# Power.net
KiCad netlist of a schematic drawn in Altium Designer
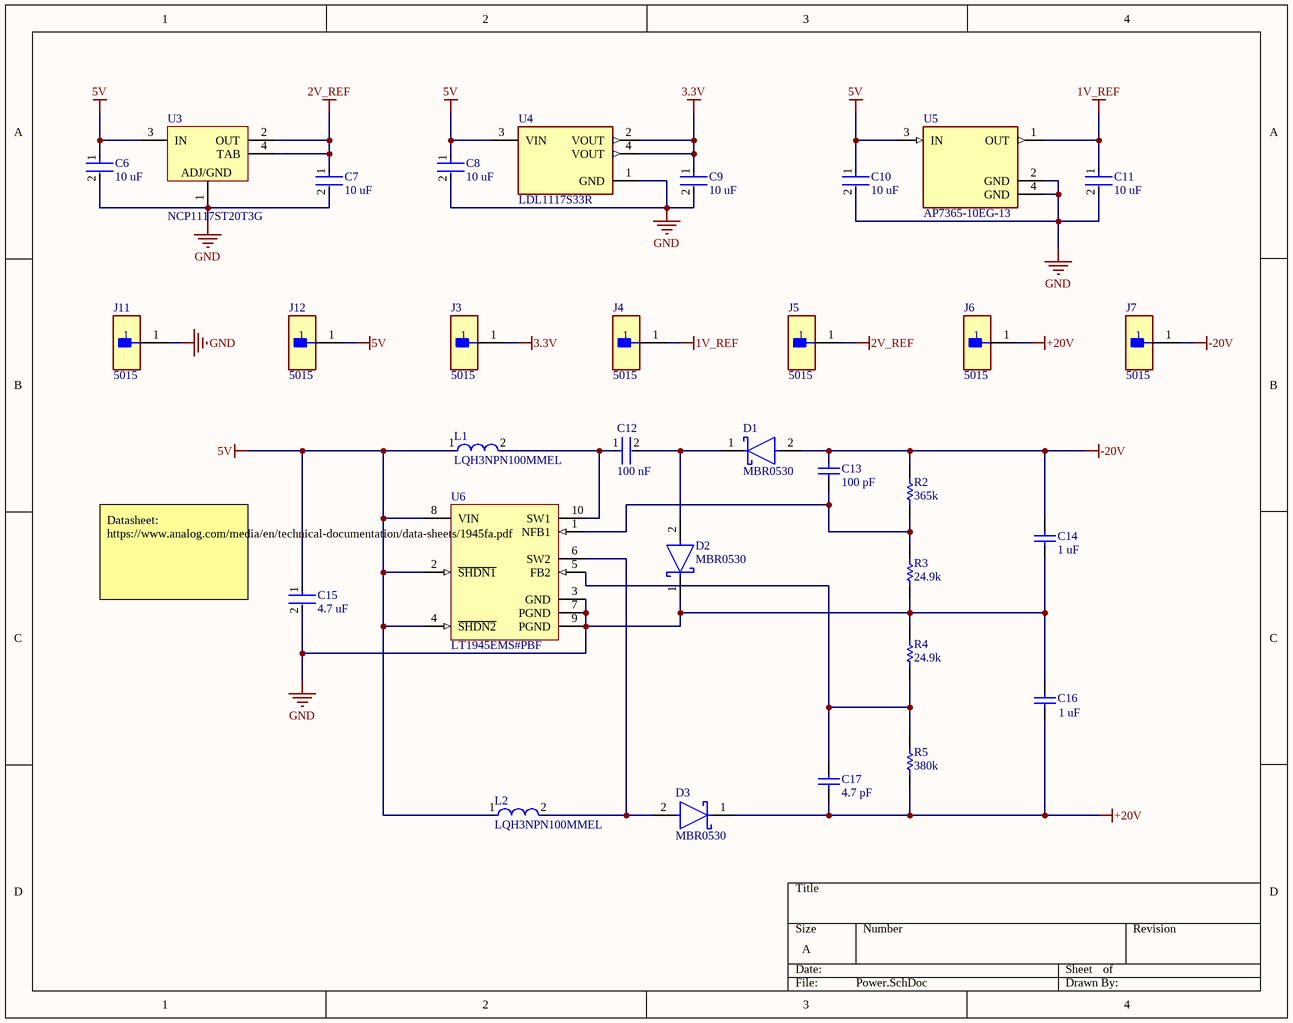
[diagram p0: Power.SchDoc]

(export (version "E")
  (design (tool "Eeschema 10.0.6"))
  (components
    (comp (ref "C6")
      (value "10 uF")
      (footprint "FP-CL21-IPC_A")
      (description "CL21 Series 0805 10uF 25V ±10% Tolerance X5R Multilayer Ceramic Chip Capacitor")
      (fields (field (name "TOLERANCE") "10%"))
      (libsource (lib "Altium Content Vault") (part "b4654b650e69147ec39a6b967a45e02"))
    )
    (comp (ref "C7")
      (value "10 uF")
      (footprint "FP-CL21-IPC_A")
      (description "CL21 Series 0805 10uF 25V ±10% Tolerance X5R Multilayer Ceramic Chip Capacitor")
      (fields (field (name "TOLERANCE") "10%"))
      (libsource (lib "Altium Content Vault") (part "b4654b650e69147ec39a6b967a45e02"))
    )
    (comp (ref "C8")
      (value "10 uF")
      (footprint "FP-CL21-IPC_A")
      (description "CL21 Series 0805 10uF 25V ±10% Tolerance X5R Multilayer Ceramic Chip Capacitor")
      (fields (field (name "TOLERANCE") "10%"))
      (libsource (lib "Altium Content Vault") (part "b4654b650e69147ec39a6b967a45e02"))
    )
    (comp (ref "C9")
      (value "10 uF")
      (footprint "FP-CL21-IPC_A")
      (description "CL21 Series 0805 10uF 25V ±10% Tolerance X5R Multilayer Ceramic Chip Capacitor")
      (fields (field (name "TOLERANCE") "10%"))
      (libsource (lib "Altium Content Vault") (part "b4654b650e69147ec39a6b967a45e02"))
    )
    (comp (ref "C10")
      (value "10 uF")
      (footprint "FP-CL21-IPC_A")
      (description "CL21 Series 0805 10uF 25V ±10% Tolerance X5R Multilayer Ceramic Chip Capacitor")
      (fields (field (name "TOLERANCE") "10%"))
      (libsource (lib "Altium Content Vault") (part "b4654b650e69147ec39a6b967a45e02"))
    )
    (comp (ref "C11")
      (value "10 uF")
      (footprint "FP-CL21-IPC_A")
      (description "CL21 Series 0805 10uF 25V ±10% Tolerance X5R Multilayer Ceramic Chip Capacitor")
      (fields (field (name "TOLERANCE") "10%"))
      (libsource (lib "Altium Content Vault") (part "b4654b650e69147ec39a6b967a45e02"))
    )
    (comp (ref "C12")
      (value "100 nF")
      (footprint "FP-C0805C-DN-MFG")
      (description "CAP CER 0.1UF 50V X7R 0805")
      (fields
        (field (name "MANUFACTURER PART NUMBER") "C0805C104K5RACTU")
        (field (name "MANUFACTURER") "KEMET")
      )
      (libsource (lib "Altium Content Vault") (part "b4654b650e69147ec39a6b967a45e02"))
    )
    (comp (ref "C13")
      (value "100 pF")
      (footprint "CAPC2013X140X50ML20T25")
      (description "08055C101KAT2A")
      (fields (field (name "MANUFACTURER") "AVX Interconnect / Elco"))
      (libsource (lib "Altium Content Vault") (part "CAP"))
    )
    (comp (ref "C14")
      (value "1 uF")
      (footprint "CAPC3216X110X50LL20T25")
      (description "C1206C105K5RACTU")
      (fields (field (name "MANUFACTURER") "Kemet") (field (name "TOLERANCE") "10%"))
      (libsource (lib "Altium Content Vault") (part "CAP-NP-2"))
    )
    (comp (ref "C15")
      (value "4.7 uF")
      (footprint "FP-C0805C475K3PACTU-MFG")
      (description "CAP CER 4.7UF 25V X5R 0805")
      (fields (field (name "TOLERANCE") "10%") (field (name "VOLTAGE") "25V"))
      (libsource (lib "Altium Content Vault") (part "02cd4be3c70576c341d710602a673aa"))
    )
    (comp (ref "C16")
      (value "1 uF")
      (footprint "CAPC3216X110X50LL20T25")
      (description "C1206C105K5RACTU")
      (fields (field (name "MANUFACTURER") "Kemet") (field (name "TOLERANCE") "10%"))
      (libsource (lib "Altium Content Vault") (part "CAP-NP-2"))
    )
    (comp (ref "C17")
      (value "4.7 pF")
      (footprint "CAPC2013X71X50ML20T25")
      (description "08055A4R7CAT2A")
      (fields (field (name "MANUFACTURER") "AVX Interconnect / Elco"))
      (libsource (lib "Altium Content Vault") (part "CAP"))
    )
    (comp (ref "D1")
      (value "MBR0530")
      (footprint "FP-425-04-MFG")
      (description "DIODE SCHOTTKY 30V 500MA SOD123")
      (libsource (lib "Altium Content Vault") (part "1d6ec82d83fb6aee721767c19dac4b9"))
    )
    (comp (ref "D2")
      (value "MBR0530")
      (footprint "FP-425-04-MFG")
      (description "DIODE SCHOTTKY 30V 500MA SOD123")
      (libsource (lib "Altium Content Vault") (part "1d6ec82d83fb6aee721767c19dac4b9"))
    )
    (comp (ref "D3")
      (value "MBR0530")
      (footprint "FP-425-04-MFG")
      (description "DIODE SCHOTTKY 30V 500MA SOD123")
      (libsource (lib "Altium Content Vault") (part "1d6ec82d83fb6aee721767c19dac4b9"))
    )
    (comp (ref "J3")
      (value "5015")
      (footprint "FP-5015-MFG")
      (description "PC TEST POINT MINIATURE")
      (fields
        (field (name "MANUFACTURER") "keystone")
        (field (name "OCTOPART") "https://octopart.com/5015-keystone-3822")
      )
      (libsource (lib "Altium Content Vault") (part "dd45045ce8184df9e99e12baf3f412c"))
    )
    (comp (ref "J4")
      (value "5015")
      (footprint "FP-5015-MFG")
      (description "PC TEST POINT MINIATURE")
      (fields
        (field (name "MANUFACTURER") "keystone")
        (field (name "OCTOPART") "https://octopart.com/5015-keystone-3822")
      )
      (libsource (lib "Altium Content Vault") (part "dd45045ce8184df9e99e12baf3f412c"))
    )
    (comp (ref "J5")
      (value "5015")
      (footprint "FP-5015-MFG")
      (description "PC TEST POINT MINIATURE")
      (fields
        (field (name "MANUFACTURER") "keystone")
        (field (name "OCTOPART") "https://octopart.com/5015-keystone-3822")
      )
      (libsource (lib "Altium Content Vault") (part "dd45045ce8184df9e99e12baf3f412c"))
    )
    (comp (ref "J6")
      (value "5015")
      (footprint "FP-5015-MFG")
      (description "PC TEST POINT MINIATURE")
      (fields
        (field (name "MANUFACTURER") "keystone")
        (field (name "OCTOPART") "https://octopart.com/5015-keystone-3822")
      )
      (libsource (lib "Altium Content Vault") (part "dd45045ce8184df9e99e12baf3f412c"))
    )
    (comp (ref "J7")
      (value "5015")
      (footprint "FP-5015-MFG")
      (description "PC TEST POINT MINIATURE")
      (fields
        (field (name "MANUFACTURER") "keystone")
        (field (name "OCTOPART") "https://octopart.com/5015-keystone-3822")
      )
      (libsource (lib "Altium Content Vault") (part "dd45045ce8184df9e99e12baf3f412c"))
    )
    (comp (ref "J11")
      (value "5015")
      (footprint "FP-5015-MFG")
      (description "PC TEST POINT MINIATURE")
      (fields
        (field (name "MANUFACTURER") "keystone")
        (field (name "OCTOPART") "https://octopart.com/5015-keystone-3822")
      )
      (libsource (lib "Altium Content Vault") (part "dd45045ce8184df9e99e12baf3f412c"))
    )
    (comp (ref "J12")
      (value "5015")
      (footprint "FP-5015-MFG")
      (description "PC TEST POINT MINIATURE")
      (fields
        (field (name "MANUFACTURER") "keystone")
        (field (name "OCTOPART") "https://octopart.com/5015-keystone-3822")
      )
      (libsource (lib "Altium Content Vault") (part "dd45045ce8184df9e99e12baf3f412c"))
    )
    (comp (ref "L1")
      (value "LQH3NPN100MMEL")
      (footprint "FP-LQH3NPH_ME-MFG")
      (description "Wire Wound Ferrite Inductor for Power Lines 10μH ±20% 0.228Ω 1280mA 1212")
      (fields (field (name "TOLERANCE") "20%"))
      (libsource (lib "Altium Content Vault") (part "725321dda6339637d4d059423bc1c3c"))
    )
    (comp (ref "L2")
      (value "LQH3NPN100MMEL")
      (footprint "FP-LQH3NPH_ME-MFG")
      (description "Wire Wound Ferrite Inductor for Power Lines 10μH ±20% 0.228Ω 1280mA 1212")
      (fields (field (name "TOLERANCE") "20%"))
      (libsource (lib "Altium Content Vault") (part "725321dda6339637d4d059423bc1c3c"))
    )
    (comp (ref "R2")
      (value "365k")
      (footprint "RESC2013X70X40NL20T20")
      (fields (field (name "PART NUMBER") "ERJ-6ENF3653V") (field (name "MANUFACTURER") "Panasonic"))
      (libsource (lib "Altium Content Vault") (part "RES"))
    )
    (comp (ref "R3")
      (value "24.9k")
      (footprint "RESC2013X70X40LL20T20")
      (fields (field (name "PART NUMBER") "ERJ-6ENF2492V") (field (name "MANUFACTURER") "Panasonic"))
      (libsource (lib "Altium Content Vault") (part "RES"))
    )
    (comp (ref "R4")
      (value "24.9k")
      (footprint "RESC2013X70X40LL20T20")
      (fields (field (name "PART NUMBER") "ERJ-6ENF2492V") (field (name "MANUFACTURER") "Panasonic"))
      (libsource (lib "Altium Content Vault") (part "RES"))
    )
    (comp (ref "R5")
      (value "380k")
      (footprint "RESC2013X70X40ML20T20")
      (fields (field (name "PART NUMBER") "ERJ-6ENF3833V") (field (name "MANUFACTURER") "Panasonic"))
      (libsource (lib "Altium Content Vault") (part "RES"))
    )
    (comp (ref "U3")
      (value "NCP1117ST20T3G")
      (footprint "ONSC-SOT-223-4-318H-01_A_V")
      (fields (field (name "TOLERANCE") "1%"))
      (libsource (lib "Altium Content Vault") (part "ONSC-NCP1117-SOT223-4"))
    )
    (comp (ref "U4")
      (value "LDL1117S33R")
      (footprint "FP-SOT223-0046067-IPC_C")
      (description "IC REG LINEAR 3.3V 1.2A SOT223")
      (fields
        (field (name "OCTOPART") "https://octopart.com/ldl1117s33r-stmicroelectronics-81876163")
        (field (name "MANUFACTURER") "STMicroelectronics")
      )
      (libsource (lib "Altium Content Vault") (part "a602d55cb6d43002de8a72f1c695f0a"))
    )
    (comp (ref "U5")
      (value "AP7365-10EG-13")
      (footprint "FP-SOT223-IPC_C")
      (description "IC REG LIN 1V 600MA SOT223-3")
      (libsource (lib "Altium Content Vault") (part "76d57bcc2558094fcdb354c83fb3a1f"))
    )
    (comp (ref "U6")
      (value "LT1945EMS#PBF")
      (footprint "LT-MS-10_N")
      (fields (field (name "MANUFACTURER") "Linear Technology"))
      (libsource (lib "Altium Content Vault") (part "LT-LT1945-MS-10"))
    )
  )
  (nets
    (net (code "1") (name "+20V") (class "Default")
      (node (ref "C16") (pin "1") (pinfunction "1_1") (pintype "passive"))
      (node (ref "C17") (pin "1") (pinfunction "1_1") (pintype "passive"))
      (node (ref "D3") (pin "1") (pinfunction "C_1") (pintype "passive"))
      (node (ref "J6") (pin "1") (pinfunction "1_1") (pintype "passive"))
      (node (ref "R5") (pin "1") (pinfunction "1_1") (pintype "passive"))
    )
    (net (code "2") (name "-20V") (class "Default")
      (node (ref "C13") (pin "1") (pinfunction "1_1") (pintype "passive"))
      (node (ref "C14") (pin "2") (pinfunction "2_2") (pintype "passive"))
      (node (ref "D1") (pin "2") (pinfunction "A_2") (pintype "passive"))
      (node (ref "J7") (pin "1") (pinfunction "1_1") (pintype "passive"))
      (node (ref "R2") (pin "2") (pinfunction "2_2") (pintype "passive"))
    )
    (net (code "3") (name "1V_REF") (class "Default")
      (node (ref "C11") (pin "1") (pinfunction "1_1") (pintype "passive"))
      (node (ref "J4") (pin "1") (pinfunction "1_1") (pintype "passive"))
      (node (ref "U5") (pin "1") (pinfunction "OUT_1") (pintype "output"))
    )
    (net (code "4") (name "2V_REF") (class "Default")
      (node (ref "C7") (pin "1") (pinfunction "1_1") (pintype "passive"))
      (node (ref "J5") (pin "1") (pinfunction "1_1") (pintype "passive"))
      (node (ref "U3") (pin "2") (pinfunction "OUT_2") (pintype "power_in"))
      (node (ref "U3") (pin "4") (pinfunction "TAB_4") (pintype "passive"))
    )
    (net (code "5") (name "3.3V") (class "Default")
      (node (ref "C9") (pin "1") (pinfunction "1_1") (pintype "passive"))
      (node (ref "J3") (pin "1") (pinfunction "1_1") (pintype "passive"))
      (node (ref "U4") (pin "2") (pinfunction "VOUT_2") (pintype "output"))
      (node (ref "U4") (pin "4") (pinfunction "VOUT_4") (pintype "output"))
    )
    (net (code "6") (name "5V") (class "Default")
      (node (ref "C10") (pin "1") (pinfunction "1_1") (pintype "passive"))
      (node (ref "C15") (pin "1") (pinfunction "1_1") (pintype "passive"))
      (node (ref "C6") (pin "1") (pinfunction "1_1") (pintype "passive"))
      (node (ref "C8") (pin "1") (pinfunction "1_1") (pintype "passive"))
      (node (ref "J12") (pin "1") (pinfunction "1_1") (pintype "passive"))
      (node (ref "L1") (pin "1") (pinfunction "1_1") (pintype "passive"))
      (node (ref "L2") (pin "1") (pinfunction "1_1") (pintype "passive"))
      (node (ref "U3") (pin "3") (pinfunction "IN_3") (pintype "power_in"))
      (node (ref "U4") (pin "3") (pinfunction "VIN_3") (pintype "power_in"))
      (node (ref "U5") (pin "3") (pinfunction "IN_3") (pintype "input"))
      (node (ref "U6") (pin "2") (pinfunction "~{SHDN1}_2") (pintype "input"))
      (node (ref "U6") (pin "4") (pinfunction "~{SHDN2}_4") (pintype "input"))
      (node (ref "U6") (pin "8") (pinfunction "VIN_8") (pintype "power_in"))
    )
    (net (code "7") (name "GND") (class "Default")
      (node (ref "C10") (pin "2") (pinfunction "2_2") (pintype "passive"))
      (node (ref "C11") (pin "2") (pinfunction "2_2") (pintype "passive"))
      (node (ref "C14") (pin "1") (pinfunction "1_1") (pintype "passive"))
      (node (ref "C15") (pin "2") (pinfunction "2_2") (pintype "passive"))
      (node (ref "C16") (pin "2") (pinfunction "2_2") (pintype "passive"))
      (node (ref "C6") (pin "2") (pinfunction "2_2") (pintype "passive"))
      (node (ref "C7") (pin "2") (pinfunction "2_2") (pintype "passive"))
      (node (ref "C8") (pin "2") (pinfunction "2_2") (pintype "passive"))
      (node (ref "C9") (pin "2") (pinfunction "2_2") (pintype "passive"))
      (node (ref "D2") (pin "1") (pinfunction "C_1") (pintype "passive"))
      (node (ref "J11") (pin "1") (pinfunction "1_1") (pintype "passive"))
      (node (ref "R3") (pin "1") (pinfunction "1_1") (pintype "passive"))
      (node (ref "R4") (pin "2") (pinfunction "2_2") (pintype "passive"))
      (node (ref "U3") (pin "1") (pinfunction "ADJ/GND_1") (pintype "passive"))
      (node (ref "U4") (pin "1") (pinfunction "GND_1") (pintype "power_in"))
      (node (ref "U5") (pin "2") (pinfunction "GND_2") (pintype "power_in"))
      (node (ref "U5") (pin "4") (pinfunction "GND_4") (pintype "power_in"))
      (node (ref "U6") (pin "3") (pinfunction "GND_3") (pintype "power_in"))
      (node (ref "U6") (pin "7") (pinfunction "PGND_7") (pintype "power_in"))
      (node (ref "U6") (pin "9") (pinfunction "PGND_9") (pintype "power_in"))
    )
    (net (code "8") (name "Net-(D1-C)") (class "Default")
      (node (ref "C12") (pin "2") (pinfunction "2_2") (pintype "passive"))
      (node (ref "D1") (pin "1") (pinfunction "C_1") (pintype "passive"))
      (node (ref "D2") (pin "2") (pinfunction "A_2") (pintype "passive"))
    )
    (net (code "9") (name "Net-(D3-A)") (class "Default")
      (node (ref "D3") (pin "2") (pinfunction "A_2") (pintype "passive"))
      (node (ref "L2") (pin "2") (pinfunction "2_2") (pintype "passive"))
      (node (ref "U6") (pin "6") (pinfunction "SW2_6") (pintype "power_in"))
    )
    (net (code "10") (name "Net-(U6-FB2)") (class "Default")
      (node (ref "C17") (pin "2") (pinfunction "2_2") (pintype "passive"))
      (node (ref "R4") (pin "1") (pinfunction "1_1") (pintype "passive"))
      (node (ref "R5") (pin "2") (pinfunction "2_2") (pintype "passive"))
      (node (ref "U6") (pin "5") (pinfunction "FB2_5") (pintype "input"))
    )
    (net (code "11") (name "Net-(U6-NFB1)") (class "Default")
      (node (ref "C13") (pin "2") (pinfunction "2_2") (pintype "passive"))
      (node (ref "R2") (pin "1") (pinfunction "1_1") (pintype "passive"))
      (node (ref "R3") (pin "2") (pinfunction "2_2") (pintype "passive"))
      (node (ref "U6") (pin "1") (pinfunction "NFB1_1") (pintype "input"))
    )
    (net (code "12") (name "Net-(U6-SW1)") (class "Default")
      (node (ref "C12") (pin "1") (pinfunction "1_1") (pintype "passive"))
      (node (ref "L1") (pin "2") (pinfunction "2_2") (pintype "passive"))
      (node (ref "U6") (pin "10") (pinfunction "SW1_10") (pintype "power_in"))
    )
  )
)
